# DAQ_Header.net
KiCad netlist of a schematic drawn in Altium Designer
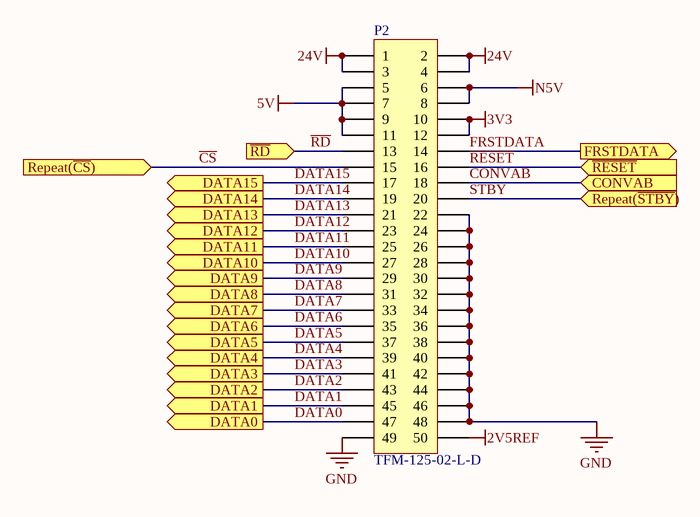
[diagram p0: DAQ_Header.SchDoc]

(export (version "E")
  (design (tool "Eeschema 10.0.6"))
  (components
    (comp (ref "P2")
      (value "TFM-125-02-L-D")
      (footprint "TFM-125-02-X-D")
      (description "Header, 25-Pin, Dual row")
      (fields (field (name "PUBLISHER") "Altium Limited"))
      (libsource (lib "Miscellaneous Connectors") (part "Header 25X2"))
    )
  )
  (nets
    (net (code "1") (name "/CONVAB") (class "Default")
      (node (ref "P2") (pin "18") (pinfunction "18_18") (pintype "passive"))
    )
    (net (code "2") (name "/DATA0") (class "Default")
      (node (ref "P2") (pin "47") (pinfunction "47_47") (pintype "passive"))
    )
    (net (code "3") (name "/DATA1") (class "Default")
      (node (ref "P2") (pin "45") (pinfunction "45_45") (pintype "passive"))
    )
    (net (code "4") (name "/DATA2") (class "Default")
      (node (ref "P2") (pin "43") (pinfunction "43_43") (pintype "passive"))
    )
    (net (code "5") (name "/DATA3") (class "Default")
      (node (ref "P2") (pin "41") (pinfunction "41_41") (pintype "passive"))
    )
    (net (code "6") (name "/DATA4") (class "Default")
      (node (ref "P2") (pin "39") (pinfunction "39_39") (pintype "passive"))
    )
    (net (code "7") (name "/DATA5") (class "Default")
      (node (ref "P2") (pin "37") (pinfunction "37_37") (pintype "passive"))
    )
    (net (code "8") (name "/DATA6") (class "Default")
      (node (ref "P2") (pin "35") (pinfunction "35_35") (pintype "passive"))
    )
    (net (code "9") (name "/DATA7") (class "Default")
      (node (ref "P2") (pin "33") (pinfunction "33_33") (pintype "passive"))
    )
    (net (code "10") (name "/DATA8") (class "Default")
      (node (ref "P2") (pin "31") (pinfunction "31_31") (pintype "passive"))
    )
    (net (code "11") (name "/DATA9") (class "Default")
      (node (ref "P2") (pin "29") (pinfunction "29_29") (pintype "passive"))
    )
    (net (code "12") (name "/DATA10") (class "Default")
      (node (ref "P2") (pin "27") (pinfunction "27_27") (pintype "passive"))
    )
    (net (code "13") (name "/DATA11") (class "Default")
      (node (ref "P2") (pin "25") (pinfunction "25_25") (pintype "passive"))
    )
    (net (code "14") (name "/DATA12") (class "Default")
      (node (ref "P2") (pin "23") (pinfunction "23_23") (pintype "passive"))
    )
    (net (code "15") (name "/DATA13") (class "Default")
      (node (ref "P2") (pin "21") (pinfunction "21_21") (pintype "passive"))
    )
    (net (code "16") (name "/DATA14") (class "Default")
      (node (ref "P2") (pin "19") (pinfunction "19_19") (pintype "passive"))
    )
    (net (code "17") (name "/DATA15") (class "Default")
      (node (ref "P2") (pin "17") (pinfunction "17_17") (pintype "passive"))
    )
    (net (code "18") (name "/FRSTDATA") (class "Default")
      (node (ref "P2") (pin "14") (pinfunction "14_14") (pintype "passive"))
    )
    (net (code "19") (name "/~{CS}") (class "Default")
      (node (ref "P2") (pin "15") (pinfunction "15_15") (pintype "passive"))
    )
    (net (code "20") (name "/~{RD}") (class "Default")
      (node (ref "P2") (pin "13") (pinfunction "13_13") (pintype "passive"))
    )
    (net (code "21") (name "/~{RESET}") (class "Default")
      (node (ref "P2") (pin "16") (pinfunction "16_16") (pintype "passive"))
    )
    (net (code "22") (name "/~{STBY}") (class "Default")
      (node (ref "P2") (pin "20") (pinfunction "20_20") (pintype "passive"))
    )
    (net (code "23") (name "2V5REF") (class "Default")
      (node (ref "P2") (pin "50") (pinfunction "50_50") (pintype "passive"))
    )
    (net (code "24") (name "3V3") (class "Default")
      (node (ref "P2") (pin "10") (pinfunction "10_10") (pintype "passive"))
      (node (ref "P2") (pin "12") (pinfunction "12_12") (pintype "passive"))
    )
    (net (code "25") (name "5V") (class "Default")
      (node (ref "P2") (pin "11") (pinfunction "11_11") (pintype "passive"))
      (node (ref "P2") (pin "5") (pinfunction "5_5") (pintype "passive"))
      (node (ref "P2") (pin "7") (pinfunction "7_7") (pintype "passive"))
      (node (ref "P2") (pin "9") (pinfunction "9_9") (pintype "passive"))
    )
    (net (code "26") (name "24V") (class "Default")
      (node (ref "P2") (pin "1") (pinfunction "1_1") (pintype "passive"))
      (node (ref "P2") (pin "2") (pinfunction "2_2") (pintype "passive"))
      (node (ref "P2") (pin "3") (pinfunction "3_3") (pintype "passive"))
      (node (ref "P2") (pin "4") (pinfunction "4_4") (pintype "passive"))
    )
    (net (code "27") (name "GND") (class "Default")
      (node (ref "P2") (pin "22") (pinfunction "22_22") (pintype "passive"))
      (node (ref "P2") (pin "24") (pinfunction "24_24") (pintype "passive"))
      (node (ref "P2") (pin "26") (pinfunction "26_26") (pintype "passive"))
      (node (ref "P2") (pin "28") (pinfunction "28_28") (pintype "passive"))
      (node (ref "P2") (pin "30") (pinfunction "30_30") (pintype "passive"))
      (node (ref "P2") (pin "32") (pinfunction "32_32") (pintype "passive"))
      (node (ref "P2") (pin "34") (pinfunction "34_34") (pintype "passive"))
      (node (ref "P2") (pin "36") (pinfunction "36_36") (pintype "passive"))
      (node (ref "P2") (pin "38") (pinfunction "38_38") (pintype "passive"))
      (node (ref "P2") (pin "40") (pinfunction "40_40") (pintype "passive"))
      (node (ref "P2") (pin "42") (pinfunction "42_42") (pintype "passive"))
      (node (ref "P2") (pin "44") (pinfunction "44_44") (pintype "passive"))
      (node (ref "P2") (pin "46") (pinfunction "46_46") (pintype "passive"))
      (node (ref "P2") (pin "48") (pinfunction "48_48") (pintype "passive"))
      (node (ref "P2") (pin "49") (pinfunction "49_49") (pintype "passive"))
    )
    (net (code "28") (name "N5V") (class "Default")
      (node (ref "P2") (pin "6") (pinfunction "6_6") (pintype "passive"))
      (node (ref "P2") (pin "8") (pinfunction "8_8") (pintype "passive"))
    )
  )
)
